# main-board.net
KiCad netlist of a schematic drawn in EAGLE
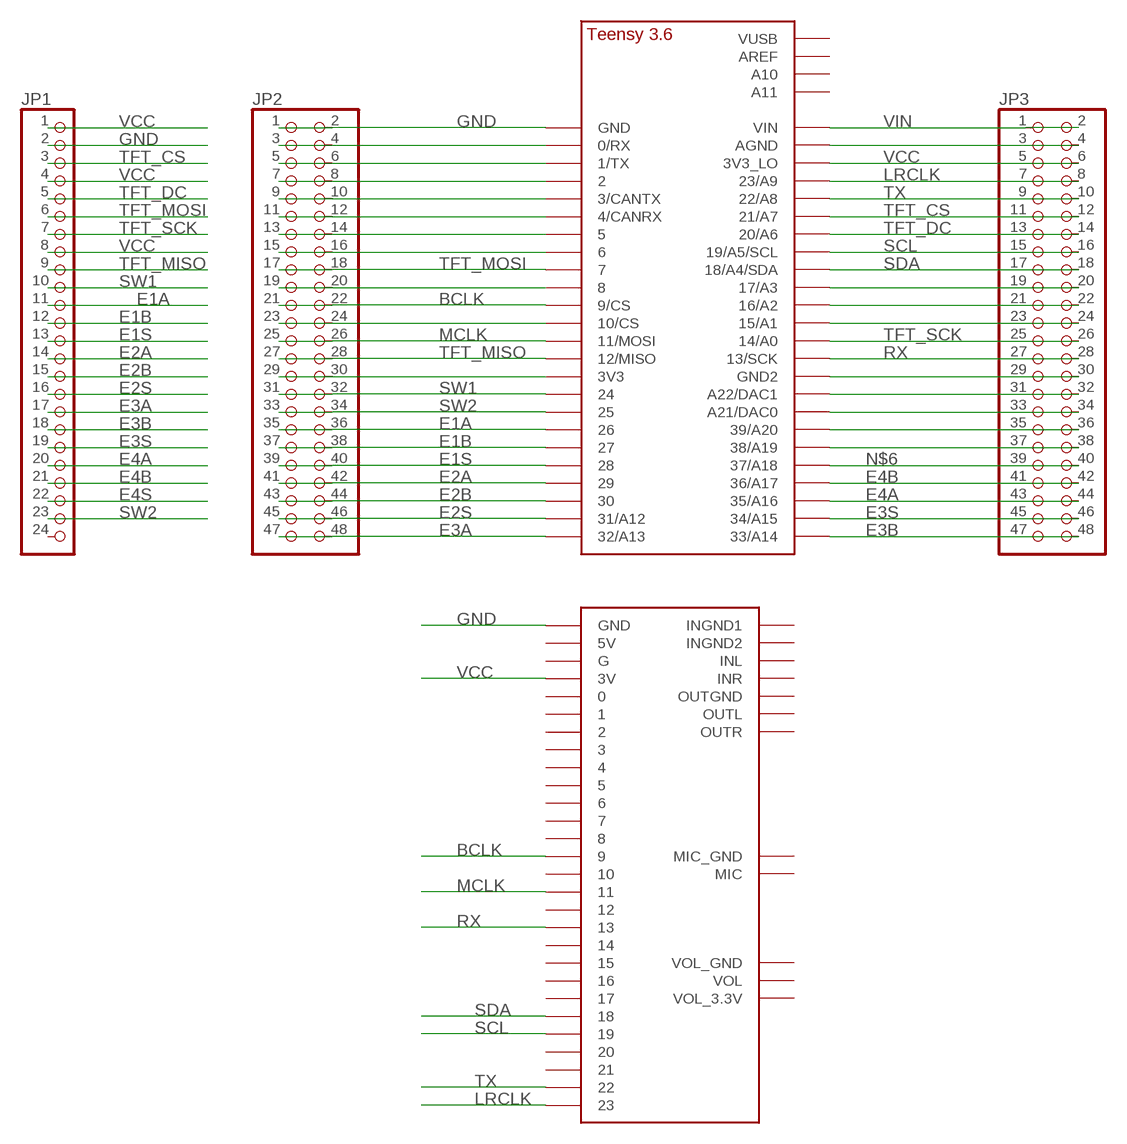
[diagram p0: schematic, sheet 1]

(export (version "E")
  (design (tool "Eeschema 10.0.6"))
  (components
    (comp (ref "JP1")
      (value "PINHD-1X24")
      (footprint "eagle-import:1X24")
      (libsource (lib "eagle-import") (part "PINHD-1X24"))
    )
    (comp (ref "JP2")
      (value "PINHD-2X24")
      (footprint "eagle-import:2X24")
      (libsource (lib "eagle-import") (part "PINHD-2X24"))
    )
    (comp (ref "JP3")
      (value "PINHD-2X24")
      (footprint "eagle-import:2X24")
      (libsource (lib "eagle-import") (part "PINHD-2X24"))
    )
    (comp (ref "U$1")
      (value "TEENSY_3.5/3.6_BASIC")
      (footprint "eagle-import:TEENSY_3.5_3.6_BASIC")
      (libsource (lib "eagle-import") (part "TEENSY_3.5/3.6_BASIC"))
    )
    (comp (ref "U$2")
      (value "AUDIOSHIELD")
      (footprint "eagle-import:AUDIOSHIELD")
      (libsource (lib "eagle-import") (part "AUDIOSHIELD"))
    )
  )
  (nets
    (net (code "1") (name "/BCLK") (class "Default")
      (node (ref "JP2") (pin "21") (pinfunction "21_21") (pintype "passive"))
      (node (ref "JP2") (pin "22") (pinfunction "22_22") (pintype "passive"))
      (node (ref "U$1") (pin "9/CS") (pinfunction "9/CS_9/CS") (pintype "bidirectional"))
      (node (ref "U$2") (pin "9") (pinfunction "9_9") (pintype "bidirectional"))
    )
    (net (code "2") (name "/E1A") (class "Default")
      (node (ref "JP1") (pin "11") (pinfunction "11_11") (pintype "passive"))
      (node (ref "JP2") (pin "35") (pinfunction "35_35") (pintype "passive"))
      (node (ref "JP2") (pin "36") (pinfunction "36_36") (pintype "passive"))
      (node (ref "U$1") (pin "26") (pinfunction "26_26") (pintype "bidirectional"))
    )
    (net (code "3") (name "/E1B") (class "Default")
      (node (ref "JP1") (pin "12") (pinfunction "12_12") (pintype "passive"))
      (node (ref "JP2") (pin "37") (pinfunction "37_37") (pintype "passive"))
      (node (ref "JP2") (pin "38") (pinfunction "38_38") (pintype "passive"))
      (node (ref "U$1") (pin "27") (pinfunction "27_27") (pintype "bidirectional"))
    )
    (net (code "4") (name "/E1S") (class "Default")
      (node (ref "JP1") (pin "13") (pinfunction "13_13") (pintype "passive"))
      (node (ref "JP2") (pin "39") (pinfunction "39_39") (pintype "passive"))
      (node (ref "JP2") (pin "40") (pinfunction "40_40") (pintype "passive"))
      (node (ref "U$1") (pin "28") (pinfunction "28_28") (pintype "bidirectional"))
    )
    (net (code "5") (name "/E2A") (class "Default")
      (node (ref "JP1") (pin "14") (pinfunction "14_14") (pintype "passive"))
      (node (ref "JP2") (pin "41") (pinfunction "41_41") (pintype "passive"))
      (node (ref "JP2") (pin "42") (pinfunction "42_42") (pintype "passive"))
      (node (ref "U$1") (pin "29") (pinfunction "29_29") (pintype "bidirectional"))
    )
    (net (code "6") (name "/E2B") (class "Default")
      (node (ref "JP1") (pin "15") (pinfunction "15_15") (pintype "passive"))
      (node (ref "JP2") (pin "43") (pinfunction "43_43") (pintype "passive"))
      (node (ref "JP2") (pin "44") (pinfunction "44_44") (pintype "passive"))
      (node (ref "U$1") (pin "30") (pinfunction "30_30") (pintype "bidirectional"))
    )
    (net (code "7") (name "/E2S") (class "Default")
      (node (ref "JP1") (pin "16") (pinfunction "16_16") (pintype "passive"))
      (node (ref "JP2") (pin "45") (pinfunction "45_45") (pintype "passive"))
      (node (ref "JP2") (pin "46") (pinfunction "46_46") (pintype "passive"))
      (node (ref "U$1") (pin "31/A12") (pinfunction "31/A12_31/A12") (pintype "bidirectional"))
    )
    (net (code "8") (name "/E3A") (class "Default")
      (node (ref "JP1") (pin "17") (pinfunction "17_17") (pintype "passive"))
      (node (ref "JP2") (pin "47") (pinfunction "47_47") (pintype "passive"))
      (node (ref "JP2") (pin "48") (pinfunction "48_48") (pintype "passive"))
      (node (ref "U$1") (pin "32/A13") (pinfunction "32/A13_32/A13") (pintype "bidirectional"))
    )
    (net (code "9") (name "/E3B") (class "Default")
      (node (ref "JP1") (pin "18") (pinfunction "18_18") (pintype "passive"))
      (node (ref "JP3") (pin "47") (pinfunction "47_47") (pintype "passive"))
      (node (ref "JP3") (pin "48") (pinfunction "48_48") (pintype "passive"))
      (node (ref "U$1") (pin "33/A14") (pinfunction "33/A14_33/A14") (pintype "bidirectional"))
    )
    (net (code "10") (name "/E3S") (class "Default")
      (node (ref "JP1") (pin "19") (pinfunction "19_19") (pintype "passive"))
      (node (ref "JP3") (pin "45") (pinfunction "45_45") (pintype "passive"))
      (node (ref "JP3") (pin "46") (pinfunction "46_46") (pintype "passive"))
      (node (ref "U$1") (pin "34/A15") (pinfunction "34/A15_34/A15") (pintype "bidirectional"))
    )
    (net (code "11") (name "/E4A") (class "Default")
      (node (ref "JP1") (pin "20") (pinfunction "20_20") (pintype "passive"))
      (node (ref "JP3") (pin "43") (pinfunction "43_43") (pintype "passive"))
      (node (ref "JP3") (pin "44") (pinfunction "44_44") (pintype "passive"))
      (node (ref "U$1") (pin "35/A16") (pinfunction "35/A16_35/A16") (pintype "bidirectional"))
    )
    (net (code "12") (name "/E4B") (class "Default")
      (node (ref "JP1") (pin "21") (pinfunction "21_21") (pintype "passive"))
      (node (ref "JP3") (pin "41") (pinfunction "41_41") (pintype "passive"))
      (node (ref "JP3") (pin "42") (pinfunction "42_42") (pintype "passive"))
      (node (ref "U$1") (pin "36/A17") (pinfunction "36/A17_36/A17") (pintype "bidirectional"))
    )
    (net (code "13") (name "/E4S") (class "Default")
      (node (ref "JP1") (pin "22") (pinfunction "22_22") (pintype "passive"))
    )
    (net (code "14") (name "/GND") (class "Default")
      (node (ref "JP1") (pin "2") (pinfunction "2_2") (pintype "passive"))
      (node (ref "JP2") (pin "1") (pinfunction "1_1") (pintype "passive"))
      (node (ref "JP2") (pin "2") (pinfunction "2_2") (pintype "passive"))
      (node (ref "U$1") (pin "GND") (pinfunction "GND_GND") (pintype "bidirectional"))
      (node (ref "U$2") (pin "GND") (pinfunction "GND_GND") (pintype "bidirectional"))
    )
    (net (code "15") (name "/LRCLK") (class "Default")
      (node (ref "JP3") (pin "7") (pinfunction "7_7") (pintype "passive"))
      (node (ref "JP3") (pin "8") (pinfunction "8_8") (pintype "passive"))
      (node (ref "U$1") (pin "23/A9") (pinfunction "23/A9_23/A9") (pintype "bidirectional"))
      (node (ref "U$2") (pin "23") (pinfunction "23_23") (pintype "bidirectional"))
    )
    (net (code "16") (name "/MCLK") (class "Default")
      (node (ref "JP2") (pin "25") (pinfunction "25_25") (pintype "passive"))
      (node (ref "JP2") (pin "26") (pinfunction "26_26") (pintype "passive"))
      (node (ref "U$1") (pin "11/MOSI") (pinfunction "11/MOSI_11/MOSI") (pintype "bidirectional"))
      (node (ref "U$2") (pin "11") (pinfunction "11_11") (pintype "bidirectional"))
    )
    (net (code "17") (name "/N$6") (class "Default")
      (node (ref "JP3") (pin "39") (pinfunction "39_39") (pintype "passive"))
      (node (ref "JP3") (pin "40") (pinfunction "40_40") (pintype "passive"))
      (node (ref "U$1") (pin "37/A18") (pinfunction "37/A18_37/A18") (pintype "bidirectional"))
    )
    (net (code "18") (name "/RX") (class "Default")
      (node (ref "JP3") (pin "27") (pinfunction "27_27") (pintype "passive"))
      (node (ref "JP3") (pin "28") (pinfunction "28_28") (pintype "passive"))
      (node (ref "U$1") (pin "13/SCK") (pinfunction "13/SCK_13/SCK") (pintype "bidirectional"))
      (node (ref "U$2") (pin "13") (pinfunction "13_13") (pintype "bidirectional"))
    )
    (net (code "19") (name "/SCL") (class "Default")
      (node (ref "JP3") (pin "15") (pinfunction "15_15") (pintype "passive"))
      (node (ref "JP3") (pin "16") (pinfunction "16_16") (pintype "passive"))
      (node (ref "U$1") (pin "19/A5/SCL") (pinfunction "19/A5/SCL_19/A5/SCL") (pintype "bidirectional"))
      (node (ref "U$2") (pin "19") (pinfunction "19_19") (pintype "bidirectional"))
    )
    (net (code "20") (name "/SDA") (class "Default")
      (node (ref "JP3") (pin "17") (pinfunction "17_17") (pintype "passive"))
      (node (ref "JP3") (pin "18") (pinfunction "18_18") (pintype "passive"))
      (node (ref "U$1") (pin "18/A4/SDA") (pinfunction "18/A4/SDA_18/A4/SDA") (pintype "bidirectional"))
      (node (ref "U$2") (pin "18") (pinfunction "18_18") (pintype "bidirectional"))
    )
    (net (code "21") (name "/SW1") (class "Default")
      (node (ref "JP1") (pin "10") (pinfunction "10_10") (pintype "passive"))
      (node (ref "JP2") (pin "31") (pinfunction "31_31") (pintype "passive"))
      (node (ref "JP2") (pin "32") (pinfunction "32_32") (pintype "passive"))
      (node (ref "U$1") (pin "24") (pinfunction "24_24") (pintype "bidirectional"))
    )
    (net (code "22") (name "/SW2") (class "Default")
      (node (ref "JP1") (pin "23") (pinfunction "23_23") (pintype "passive"))
      (node (ref "JP2") (pin "33") (pinfunction "33_33") (pintype "passive"))
      (node (ref "JP2") (pin "34") (pinfunction "34_34") (pintype "passive"))
      (node (ref "U$1") (pin "25") (pinfunction "25_25") (pintype "bidirectional"))
    )
    (net (code "23") (name "/TFT_CS") (class "Default")
      (node (ref "JP1") (pin "3") (pinfunction "3_3") (pintype "passive"))
      (node (ref "JP3") (pin "11") (pinfunction "11_11") (pintype "passive"))
      (node (ref "JP3") (pin "12") (pinfunction "12_12") (pintype "passive"))
      (node (ref "U$1") (pin "21/A7") (pinfunction "21/A7_21/A7") (pintype "bidirectional"))
    )
    (net (code "24") (name "/TFT_DC") (class "Default")
      (node (ref "JP1") (pin "5") (pinfunction "5_5") (pintype "passive"))
      (node (ref "JP3") (pin "13") (pinfunction "13_13") (pintype "passive"))
      (node (ref "JP3") (pin "14") (pinfunction "14_14") (pintype "passive"))
      (node (ref "U$1") (pin "20/A6") (pinfunction "20/A6_20/A6") (pintype "bidirectional"))
    )
    (net (code "25") (name "/TFT_MISO") (class "Default")
      (node (ref "JP1") (pin "9") (pinfunction "9_9") (pintype "passive"))
      (node (ref "JP2") (pin "27") (pinfunction "27_27") (pintype "passive"))
      (node (ref "JP2") (pin "28") (pinfunction "28_28") (pintype "passive"))
      (node (ref "U$1") (pin "12/MISO") (pinfunction "12/MISO_12/MISO") (pintype "bidirectional"))
    )
    (net (code "26") (name "/TFT_MOSI") (class "Default")
      (node (ref "JP1") (pin "6") (pinfunction "6_6") (pintype "passive"))
      (node (ref "JP2") (pin "17") (pinfunction "17_17") (pintype "passive"))
      (node (ref "JP2") (pin "18") (pinfunction "18_18") (pintype "passive"))
      (node (ref "U$1") (pin "7") (pinfunction "7_7") (pintype "bidirectional"))
    )
    (net (code "27") (name "/TFT_SCK") (class "Default")
      (node (ref "JP1") (pin "7") (pinfunction "7_7") (pintype "passive"))
      (node (ref "JP3") (pin "25") (pinfunction "25_25") (pintype "passive"))
      (node (ref "JP3") (pin "26") (pinfunction "26_26") (pintype "passive"))
      (node (ref "U$1") (pin "14/A0") (pinfunction "14/A0_14/A0") (pintype "bidirectional"))
    )
    (net (code "28") (name "/TX") (class "Default")
      (node (ref "JP3") (pin "10") (pinfunction "10_10") (pintype "passive"))
      (node (ref "JP3") (pin "9") (pinfunction "9_9") (pintype "passive"))
      (node (ref "U$1") (pin "22/A8") (pinfunction "22/A8_22/A8") (pintype "bidirectional"))
      (node (ref "U$2") (pin "22") (pinfunction "22_22") (pintype "bidirectional"))
    )
    (net (code "29") (name "/VCC") (class "Default")
      (node (ref "JP1") (pin "1") (pinfunction "1_1") (pintype "passive"))
      (node (ref "JP1") (pin "4") (pinfunction "4_4") (pintype "passive"))
      (node (ref "JP1") (pin "8") (pinfunction "8_8") (pintype "passive"))
      (node (ref "JP3") (pin "5") (pinfunction "5_5") (pintype "passive"))
      (node (ref "JP3") (pin "6") (pinfunction "6_6") (pintype "passive"))
      (node (ref "U$1") (pin "3V3_LO") (pinfunction "3V3_LO_3V3_LO") (pintype "bidirectional"))
      (node (ref "U$2") (pin "3V") (pinfunction "3V_3V") (pintype "bidirectional"))
    )
    (net (code "30") (name "/VIN") (class "Default")
      (node (ref "JP3") (pin "1") (pinfunction "1_1") (pintype "passive"))
      (node (ref "JP3") (pin "2") (pinfunction "2_2") (pintype "passive"))
      (node (ref "U$1") (pin "VIN") (pinfunction "VIN_VIN") (pintype "bidirectional"))
    )
    (net (code "31") (name "Net-(JP2-Pad3)") (class "Default")
      (node (ref "JP2") (pin "3") (pinfunction "3_3") (pintype "passive"))
      (node (ref "JP2") (pin "4") (pinfunction "4_4") (pintype "passive"))
      (node (ref "U$1") (pin "0/RX") (pinfunction "0/RX_0/RX") (pintype "bidirectional"))
    )
    (net (code "32") (name "Net-(JP2-Pad5)") (class "Default")
      (node (ref "JP2") (pin "5") (pinfunction "5_5") (pintype "passive"))
      (node (ref "JP2") (pin "6") (pinfunction "6_6") (pintype "passive"))
      (node (ref "U$1") (pin "1/TX") (pinfunction "1/TX_1/TX") (pintype "bidirectional"))
    )
    (net (code "33") (name "Net-(JP2-Pad7)") (class "Default")
      (node (ref "JP2") (pin "7") (pinfunction "7_7") (pintype "passive"))
      (node (ref "JP2") (pin "8") (pinfunction "8_8") (pintype "passive"))
      (node (ref "U$1") (pin "2") (pinfunction "2_2") (pintype "bidirectional"))
    )
    (net (code "34") (name "Net-(JP2-Pad10)") (class "Default")
      (node (ref "JP2") (pin "10") (pinfunction "10_10") (pintype "passive"))
      (node (ref "JP2") (pin "9") (pinfunction "9_9") (pintype "passive"))
      (node (ref "U$1") (pin "3/CANTX") (pinfunction "3/CANTX_3/CANTX") (pintype "bidirectional"))
    )
    (net (code "35") (name "Net-(JP2-Pad11)") (class "Default")
      (node (ref "JP2") (pin "11") (pinfunction "11_11") (pintype "passive"))
      (node (ref "JP2") (pin "12") (pinfunction "12_12") (pintype "passive"))
      (node (ref "U$1") (pin "4/CANRX") (pinfunction "4/CANRX_4/CANRX") (pintype "bidirectional"))
    )
    (net (code "36") (name "Net-(JP2-Pad13)") (class "Default")
      (node (ref "JP2") (pin "13") (pinfunction "13_13") (pintype "passive"))
      (node (ref "JP2") (pin "14") (pinfunction "14_14") (pintype "passive"))
      (node (ref "U$1") (pin "5") (pinfunction "5_5") (pintype "bidirectional"))
    )
    (net (code "37") (name "Net-(JP2-Pad15)") (class "Default")
      (node (ref "JP2") (pin "15") (pinfunction "15_15") (pintype "passive"))
      (node (ref "JP2") (pin "16") (pinfunction "16_16") (pintype "passive"))
      (node (ref "U$1") (pin "6") (pinfunction "6_6") (pintype "bidirectional"))
    )
    (net (code "38") (name "Net-(JP2-Pad19)") (class "Default")
      (node (ref "JP2") (pin "19") (pinfunction "19_19") (pintype "passive"))
      (node (ref "JP2") (pin "20") (pinfunction "20_20") (pintype "passive"))
      (node (ref "U$1") (pin "8") (pinfunction "8_8") (pintype "bidirectional"))
    )
    (net (code "39") (name "Net-(JP2-Pad23)") (class "Default")
      (node (ref "JP2") (pin "23") (pinfunction "23_23") (pintype "passive"))
      (node (ref "JP2") (pin "24") (pinfunction "24_24") (pintype "passive"))
      (node (ref "U$1") (pin "10/CS") (pinfunction "10/CS_10/CS") (pintype "bidirectional"))
    )
    (net (code "40") (name "Net-(JP2-Pad29)") (class "Default")
      (node (ref "JP2") (pin "29") (pinfunction "29_29") (pintype "passive"))
      (node (ref "JP2") (pin "30") (pinfunction "30_30") (pintype "passive"))
      (node (ref "U$1") (pin "3V3") (pinfunction "3V3_3V3") (pintype "bidirectional"))
    )
    (net (code "41") (name "Net-(JP3-Pad3)") (class "Default")
      (node (ref "JP3") (pin "3") (pinfunction "3_3") (pintype "passive"))
      (node (ref "JP3") (pin "4") (pinfunction "4_4") (pintype "passive"))
      (node (ref "U$1") (pin "AGND") (pinfunction "AGND_AGND") (pintype "bidirectional"))
    )
    (net (code "42") (name "Net-(JP3-Pad19)") (class "Default")
      (node (ref "JP3") (pin "19") (pinfunction "19_19") (pintype "passive"))
      (node (ref "JP3") (pin "20") (pinfunction "20_20") (pintype "passive"))
      (node (ref "U$1") (pin "17/A3") (pinfunction "17/A3_17/A3") (pintype "bidirectional"))
    )
    (net (code "43") (name "Net-(JP3-Pad21)") (class "Default")
      (node (ref "JP3") (pin "21") (pinfunction "21_21") (pintype "passive"))
      (node (ref "JP3") (pin "22") (pinfunction "22_22") (pintype "passive"))
      (node (ref "U$1") (pin "16/A2") (pinfunction "16/A2_16/A2") (pintype "bidirectional"))
    )
    (net (code "44") (name "Net-(JP3-Pad23)") (class "Default")
      (node (ref "JP3") (pin "23") (pinfunction "23_23") (pintype "passive"))
      (node (ref "JP3") (pin "24") (pinfunction "24_24") (pintype "passive"))
      (node (ref "U$1") (pin "15/A1") (pinfunction "15/A1_15/A1") (pintype "bidirectional"))
    )
    (net (code "45") (name "Net-(JP3-Pad29)") (class "Default")
      (node (ref "JP3") (pin "29") (pinfunction "29_29") (pintype "passive"))
      (node (ref "JP3") (pin "30") (pinfunction "30_30") (pintype "passive"))
      (node (ref "U$1") (pin "GND2") (pinfunction "GND2_GND2") (pintype "bidirectional"))
    )
    (net (code "46") (name "Net-(JP3-Pad31)") (class "Default")
      (node (ref "JP3") (pin "31") (pinfunction "31_31") (pintype "passive"))
      (node (ref "JP3") (pin "32") (pinfunction "32_32") (pintype "passive"))
      (node (ref "U$1") (pin "A22/DAC1") (pinfunction "A22/DAC1_A22/DAC1") (pintype "bidirectional"))
    )
    (net (code "47") (name "Net-(JP3-Pad35)") (class "Default")
      (node (ref "JP3") (pin "35") (pinfunction "35_35") (pintype "passive"))
      (node (ref "JP3") (pin "36") (pinfunction "36_36") (pintype "passive"))
      (node (ref "U$1") (pin "39/A20") (pinfunction "39/A20_39/A20") (pintype "bidirectional"))
    )
    (net (code "48") (name "Net-(JP3-Pad37)") (class "Default")
      (node (ref "JP3") (pin "37") (pinfunction "37_37") (pintype "passive"))
      (node (ref "JP3") (pin "38") (pinfunction "38_38") (pintype "passive"))
      (node (ref "U$1") (pin "38/A19") (pinfunction "38/A19_38/A19") (pintype "bidirectional"))
    )
    (net (code "49") (name "Net-(U$1-A21{slash}DAC0)") (class "Default")
      (node (ref "JP3") (pin "33") (pinfunction "33_33") (pintype "passive"))
      (node (ref "JP3") (pin "34") (pinfunction "34_34") (pintype "passive"))
      (node (ref "U$1") (pin "21/DAC0") (pinfunction "A21/DAC0_21/DAC0") (pintype "bidirectional"))
    )
    (net (code "50") (name "unconnected-(JP1-Pad24)") (class "Default")
      (node (ref "JP1") (pin "24") (pinfunction "24_24") (pintype "passive"))
    )
    (net (code "51") (name "unconnected-(U$1-PadA10)") (class "Default")
      (node (ref "U$1") (pin "A10") (pinfunction "A10_A10") (pintype "bidirectional"))
    )
    (net (code "52") (name "unconnected-(U$1-PadA11)") (class "Default")
      (node (ref "U$1") (pin "A11") (pinfunction "A11_A11") (pintype "bidirectional"))
    )
    (net (code "53") (name "unconnected-(U$1-PadAREF)") (class "Default")
      (node (ref "U$1") (pin "AREF") (pinfunction "AREF_AREF") (pintype "bidirectional"))
    )
    (net (code "54") (name "unconnected-(U$1-PadVUSB)") (class "Default")
      (node (ref "U$1") (pin "VUSB") (pinfunction "VUSB_VUSB") (pintype "bidirectional"))
    )
    (net (code "55") (name "unconnected-(U$2-MIC_GND-PadGND_MIC)") (class "Default")
      (node (ref "U$2") (pin "GND_MIC") (pinfunction "MIC_GND_GND_MIC") (pintype "bidirectional"))
    )
    (net (code "56") (name "unconnected-(U$2-Pad0)") (class "Default")
      (node (ref "U$2") (pin "0") (pinfunction "0_0") (pintype "bidirectional"))
    )
    (net (code "57") (name "unconnected-(U$2-Pad1)") (class "Default")
      (node (ref "U$2") (pin "1") (pinfunction "1_1") (pintype "bidirectional"))
    )
    (net (code "58") (name "unconnected-(U$2-Pad2)") (class "Default")
      (node (ref "U$2") (pin "2") (pinfunction "2_2") (pintype "bidirectional"))
    )
    (net (code "59") (name "unconnected-(U$2-Pad3)") (class "Default")
      (node (ref "U$2") (pin "3") (pinfunction "3_3") (pintype "bidirectional"))
    )
    (net (code "60") (name "unconnected-(U$2-Pad4)") (class "Default")
      (node (ref "U$2") (pin "4") (pinfunction "4_4") (pintype "bidirectional"))
    )
    (net (code "61") (name "unconnected-(U$2-Pad5)") (class "Default")
      (node (ref "U$2") (pin "5") (pinfunction "5_5") (pintype "bidirectional"))
    )
    (net (code "62") (name "unconnected-(U$2-Pad5V)") (class "Default")
      (node (ref "U$2") (pin "5V") (pinfunction "5V_5V") (pintype "bidirectional"))
    )
    (net (code "63") (name "unconnected-(U$2-Pad6)") (class "Default")
      (node (ref "U$2") (pin "6") (pinfunction "6_6") (pintype "bidirectional"))
    )
    (net (code "64") (name "unconnected-(U$2-Pad7)") (class "Default")
      (node (ref "U$2") (pin "7") (pinfunction "7_7") (pintype "bidirectional"))
    )
    (net (code "65") (name "unconnected-(U$2-Pad8)") (class "Default")
      (node (ref "U$2") (pin "8") (pinfunction "8_8") (pintype "bidirectional"))
    )
    (net (code "66") (name "unconnected-(U$2-Pad10)") (class "Default")
      (node (ref "U$2") (pin "10") (pinfunction "10_10") (pintype "bidirectional"))
    )
    (net (code "67") (name "unconnected-(U$2-Pad12)") (class "Default")
      (node (ref "U$2") (pin "12") (pinfunction "12_12") (pintype "bidirectional"))
    )
    (net (code "68") (name "unconnected-(U$2-Pad14)") (class "Default")
      (node (ref "U$2") (pin "14") (pinfunction "14_14") (pintype "bidirectional"))
    )
    (net (code "69") (name "unconnected-(U$2-Pad15)") (class "Default")
      (node (ref "U$2") (pin "15") (pinfunction "15_15") (pintype "bidirectional"))
    )
    (net (code "70") (name "unconnected-(U$2-Pad16)") (class "Default")
      (node (ref "U$2") (pin "16") (pinfunction "16_16") (pintype "bidirectional"))
    )
    (net (code "71") (name "unconnected-(U$2-Pad17)") (class "Default")
      (node (ref "U$2") (pin "17") (pinfunction "17_17") (pintype "bidirectional"))
    )
    (net (code "72") (name "unconnected-(U$2-Pad20)") (class "Default")
      (node (ref "U$2") (pin "20") (pinfunction "20_20") (pintype "bidirectional"))
    )
    (net (code "73") (name "unconnected-(U$2-Pad21)") (class "Default")
      (node (ref "U$2") (pin "21") (pinfunction "21_21") (pintype "bidirectional"))
    )
    (net (code "74") (name "unconnected-(U$2-PadG)") (class "Default")
      (node (ref "U$2") (pin "G") (pinfunction "G_G") (pintype "bidirectional"))
    )
    (net (code "75") (name "unconnected-(U$2-PadINGND1)") (class "Default")
      (node (ref "U$2") (pin "INGND1") (pinfunction "INGND1_INGND1") (pintype "bidirectional"))
    )
    (net (code "76") (name "unconnected-(U$2-PadINGND2)") (class "Default")
      (node (ref "U$2") (pin "INGND2") (pinfunction "INGND2_INGND2") (pintype "bidirectional"))
    )
    (net (code "77") (name "unconnected-(U$2-PadINL)") (class "Default")
      (node (ref "U$2") (pin "INL") (pinfunction "INL_INL") (pintype "input"))
    )
    (net (code "78") (name "unconnected-(U$2-PadINR)") (class "Default")
      (node (ref "U$2") (pin "INR") (pinfunction "INR_INR") (pintype "input"))
    )
    (net (code "79") (name "unconnected-(U$2-PadMIC)") (class "Default")
      (node (ref "U$2") (pin "MIC") (pinfunction "MIC_MIC") (pintype "input"))
    )
    (net (code "80") (name "unconnected-(U$2-PadOUTGND)") (class "Default")
      (node (ref "U$2") (pin "OUTGND") (pinfunction "OUTGND_OUTGND") (pintype "bidirectional"))
    )
    (net (code "81") (name "unconnected-(U$2-PadOUTL)") (class "Default")
      (node (ref "U$2") (pin "OUTL") (pinfunction "OUTL_OUTL") (pintype "output"))
    )
    (net (code "82") (name "unconnected-(U$2-PadOUTR)") (class "Default")
      (node (ref "U$2") (pin "OUTR") (pinfunction "OUTR_OUTR") (pintype "output"))
    )
    (net (code "83") (name "unconnected-(U$2-PadVOL)") (class "Default")
      (node (ref "U$2") (pin "VOL") (pinfunction "VOL_VOL") (pintype "input"))
    )
    (net (code "84") (name "unconnected-(U$2-PadVOL_3.3V)") (class "Default")
      (node (ref "U$2") (pin "VOL_3.3V") (pinfunction "VOL_3.3V_VOL_3.3V") (pintype "bidirectional"))
    )
    (net (code "85") (name "unconnected-(U$2-PadVOL_GND)") (class "Default")
      (node (ref "U$2") (pin "VOL_GND") (pinfunction "VOL_GND_VOL_GND") (pintype "bidirectional"))
    )
  )
)
